# Logic.net
KiCad netlist of a schematic drawn in Altium Designer
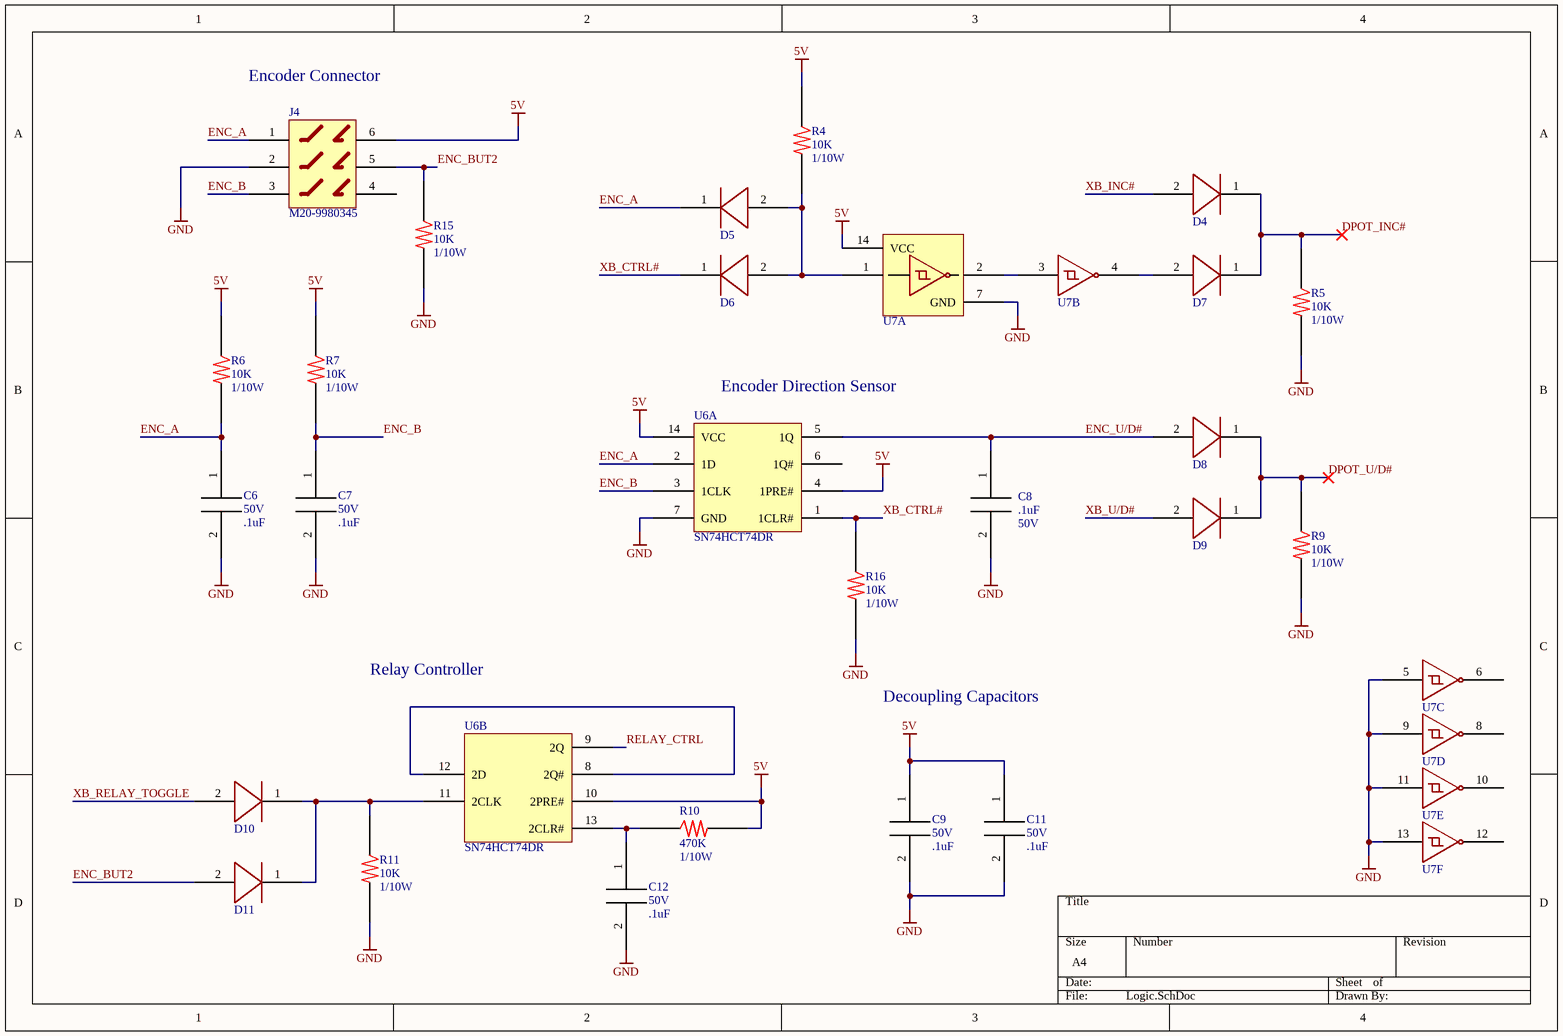
[diagram p0: Logic.SchDoc]

(export (version "E")
  (design (tool "Eeschema 10.0.6"))
  (components
    (comp (ref "C6")
      (value ".1uF")
      (footprint "0603")
      (fields
        (field (name "PARTNUMBER") "C0603C104K5RACAUTO")
        (field (name "MANUFACTURER") "KEMET")
        (field (name "RATING") "50V")
        (field (name "Comment") "C_CAP_0603")
      )
      (libsource (lib "SeniorProject") (part "C_CAP_0603"))
    )
    (comp (ref "C7")
      (value ".1uF")
      (footprint "0603")
      (fields
        (field (name "PARTNUMBER") "C0603C104K5RACAUTO")
        (field (name "MANUFACTURER") "KEMET")
        (field (name "RATING") "50V")
        (field (name "Comment") "C_CAP_0603")
      )
      (libsource (lib "SeniorProject") (part "C_CAP_0603"))
    )
    (comp (ref "C8")
      (value ".1uF")
      (footprint "0603")
      (fields
        (field (name "PARTNUMBER") "C0603C104K5RACAUTO")
        (field (name "MANUFACTURER") "KEMET")
        (field (name "RATING") "50V")
        (field (name "Comment") "C_CAP_0603")
      )
      (libsource (lib "SeniorProject") (part "C_CAP_0603"))
    )
    (comp (ref "C9")
      (value ".1uF")
      (footprint "0603")
      (fields
        (field (name "PARTNUMBER") "C0603C104K5RACAUTO")
        (field (name "MANUFACTURER") "KEMET")
        (field (name "RATING") "50V")
        (field (name "Comment") "C_CAP_0603")
      )
      (libsource (lib "SeniorProject") (part "C_CAP_0603"))
    )
    (comp (ref "C11")
      (value ".1uF")
      (footprint "0603")
      (fields
        (field (name "PARTNUMBER") "C0603C104K5RACAUTO")
        (field (name "MANUFACTURER") "KEMET")
        (field (name "RATING") "50V")
        (field (name "Comment") "C_CAP_0603")
      )
      (libsource (lib "SeniorProject") (part "C_CAP_0603"))
    )
    (comp (ref "C12")
      (value ".1uF")
      (footprint "0603")
      (fields
        (field (name "PARTNUMBER") "C0603C104K5RACAUTO")
        (field (name "MANUFACTURER") "KEMET")
        (field (name "RATING") "50V")
        (field (name "Comment") "C_CAP_0603")
      )
      (libsource (lib "SeniorProject") (part "C_CAP_0603"))
    )
    (comp (ref "D4")
      (value "D_DIODE_SOD123")
      (footprint "SOD123")
      (fields (field (name "PARTNUMBER") "BAS16GWJ") (field (name "MANUFACTURER") "Nexperia USA Inc"))
      (libsource (lib "SeniorProject") (part "D_DIODE_SOD123"))
    )
    (comp (ref "D5")
      (value "D_DIODE_SOD123")
      (footprint "SOD123")
      (fields (field (name "PARTNUMBER") "BAS16GWJ") (field (name "MANUFACTURER") "Nexperia USA Inc"))
      (libsource (lib "SeniorProject") (part "D_DIODE_SOD123"))
    )
    (comp (ref "D6")
      (value "D_DIODE_SOD123")
      (footprint "SOD123")
      (fields (field (name "PARTNUMBER") "BAS16GWJ") (field (name "MANUFACTURER") "Nexperia USA Inc"))
      (libsource (lib "SeniorProject") (part "D_DIODE_SOD123"))
    )
    (comp (ref "D7")
      (value "D_DIODE_SOD123")
      (footprint "SOD123")
      (fields (field (name "PARTNUMBER") "BAS16GWJ") (field (name "MANUFACTURER") "Nexperia USA Inc"))
      (libsource (lib "SeniorProject") (part "D_DIODE_SOD123"))
    )
    (comp (ref "D8")
      (value "D_DIODE_SOD123")
      (footprint "SOD123")
      (fields (field (name "PARTNUMBER") "BAS16GWJ") (field (name "MANUFACTURER") "Nexperia USA Inc"))
      (libsource (lib "SeniorProject") (part "D_DIODE_SOD123"))
    )
    (comp (ref "D9")
      (value "D_DIODE_SOD123")
      (footprint "SOD123")
      (fields (field (name "PARTNUMBER") "BAS16GWJ") (field (name "MANUFACTURER") "Nexperia USA Inc"))
      (libsource (lib "SeniorProject") (part "D_DIODE_SOD123"))
    )
    (comp (ref "D10")
      (value "D_DIODE_SOD123")
      (footprint "SOD123")
      (fields (field (name "PARTNUMBER") "BAS16GWJ") (field (name "MANUFACTURER") "Nexperia USA Inc"))
      (libsource (lib "SeniorProject") (part "D_DIODE_SOD123"))
    )
    (comp (ref "D11")
      (value "D_DIODE_SOD123")
      (footprint "SOD123")
      (fields (field (name "PARTNUMBER") "BAS16GWJ") (field (name "MANUFACTURER") "Nexperia USA Inc"))
      (libsource (lib "SeniorProject") (part "D_DIODE_SOD123"))
    )
    (comp (ref "J4")
      (value "J_6POSM_M20-9980345")
      (footprint "M20-9980345")
      (fields (field (name "MANUFACTURER") "Harwin") (field (name "PARTNUMBER") "M20-9980345"))
      (libsource (lib "SeniorProject") (part "J_6POSM_M20-9980345"))
    )
    (comp (ref "R4")
      (value "10K")
      (footprint "0603")
      (fields
        (field (name "PARTNUMBER") "RC0603JR-0710KL")
        (field (name "RATING") "1/10W")
        (field (name "Comment") "R_RES_0603")
      )
      (libsource (lib "SeniorProject") (part "R_RES_0603"))
    )
    (comp (ref "R5")
      (value "10K")
      (footprint "0603")
      (fields
        (field (name "PARTNUMBER") "RC0603JR-0710KL")
        (field (name "RATING") "1/10W")
        (field (name "Comment") "R_RES_0603")
      )
      (libsource (lib "SeniorProject") (part "R_RES_0603"))
    )
    (comp (ref "R6")
      (value "10K")
      (footprint "0603")
      (fields
        (field (name "PARTNUMBER") "RC0603JR-0710KL")
        (field (name "RATING") "1/10W")
        (field (name "Comment") "R_RES_0603")
      )
      (libsource (lib "SeniorProject") (part "R_RES_0603"))
    )
    (comp (ref "R7")
      (value "10K")
      (footprint "0603")
      (fields
        (field (name "PARTNUMBER") "RC0603JR-0710KL")
        (field (name "RATING") "1/10W")
        (field (name "Comment") "R_RES_0603")
      )
      (libsource (lib "SeniorProject") (part "R_RES_0603"))
    )
    (comp (ref "R9")
      (value "10K")
      (footprint "0603")
      (fields
        (field (name "PARTNUMBER") "RC0603JR-0710KL")
        (field (name "RATING") "1/10W")
        (field (name "Comment") "R_RES_0603")
      )
      (libsource (lib "SeniorProject") (part "R_RES_0603"))
    )
    (comp (ref "R10")
      (value "470K")
      (footprint "0603")
      (fields
        (field (name "PARTNUMBER") "RC0603JR-07470KL")
        (field (name "MANUFACTURER") "Yageo")
        (field (name "RATING") "1/10W")
        (field (name "Comment") "R_RES_0603")
      )
      (libsource (lib "SeniorProject") (part "R_RES_0603"))
    )
    (comp (ref "R11")
      (value "10K")
      (footprint "0603")
      (fields
        (field (name "PARTNUMBER") "RC0603JR-0710KL")
        (field (name "RATING") "1/10W")
        (field (name "Comment") "R_RES_0603")
      )
      (libsource (lib "SeniorProject") (part "R_RES_0603"))
    )
    (comp (ref "R15")
      (value "10K")
      (footprint "0603")
      (fields
        (field (name "PARTNUMBER") "RC0603JR-0710KL")
        (field (name "RATING") "1/10W")
        (field (name "Comment") "R_RES_0603")
      )
      (libsource (lib "SeniorProject") (part "R_RES_0603"))
    )
    (comp (ref "R16")
      (value "10K")
      (footprint "0603")
      (fields
        (field (name "PARTNUMBER") "RC0603JR-0710KL")
        (field (name "RATING") "1/10W")
        (field (name "Comment") "R_RES_0603")
      )
      (libsource (lib "SeniorProject") (part "R_RES_0603"))
    )
    (comp (ref "U6")
      (value "U_DUALDFLIP_SOIC14")
      (footprint "SOIC14")
      (fields (field (name "MANUFACTURER") "TI") (field (name "PARTNUMBER") "SN74HCT74DR"))
      (libsource (lib "SeniorProject") (part "U_DUALDFLIP_SOIC14"))
    )
    (comp (ref "U7")
      (value "U_SN74HCT04DR_SOIC14")
      (footprint "SOIC14")
      (fields (field (name "PARTNUMBER") "SN74HCT04DR") (field (name "MANUFACTURER") "TI"))
      (libsource (lib "SeniorProject") (part "U_SN74HCT04DR_SOIC14"))
    )
  )
  (nets
    (net (code "1") (name "/DPOT_INC#") (class "Default")
      (node (ref "D4") (pin "1") (pintype "passive"))
      (node (ref "D7") (pin "1") (pintype "passive"))
      (node (ref "R5") (pin "1") (pintype "passive"))
    )
    (net (code "2") (name "/DPOT_U{slash}D#") (class "Default")
      (node (ref "D8") (pin "1") (pintype "passive"))
      (node (ref "D9") (pin "1") (pintype "passive"))
      (node (ref "R9") (pin "1") (pintype "passive"))
    )
    (net (code "3") (name "/ENC_A") (class "Default")
      (node (ref "C6") (pin "1") (pintype "passive"))
      (node (ref "D5") (pin "1") (pintype "passive"))
      (node (ref "J4") (pin "1") (pinfunction "1_1") (pintype "passive"))
      (node (ref "R6") (pin "2") (pintype "passive"))
      (node (ref "U6") (pin "2") (pinfunction "1D_2") (pintype "passive"))
    )
    (net (code "4") (name "/ENC_B") (class "Default")
      (node (ref "C7") (pin "1") (pintype "passive"))
      (node (ref "J4") (pin "3") (pinfunction "3_3") (pintype "passive"))
      (node (ref "R7") (pin "2") (pintype "passive"))
      (node (ref "U6") (pin "3") (pinfunction "1CLK_3") (pintype "passive"))
    )
    (net (code "5") (name "/ENC_BUT2") (class "Default")
      (node (ref "D11") (pin "2") (pintype "passive"))
      (node (ref "J4") (pin "5") (pinfunction "5_5") (pintype "passive"))
      (node (ref "R15") (pin "1") (pintype "passive"))
    )
    (net (code "6") (name "/ENC_U{slash}D#") (class "Default")
      (node (ref "C8") (pin "1") (pintype "passive"))
      (node (ref "D8") (pin "2") (pintype "passive"))
      (node (ref "U6") (pin "5") (pinfunction "1Q_5") (pintype "passive"))
    )
    (net (code "7") (name "/RELAY_CTRL") (class "Default")
      (node (ref "U6") (pin "9") (pinfunction "2Q_9") (pintype "passive"))
    )
    (net (code "8") (name "/XB_CTRL#") (class "Default")
      (node (ref "D6") (pin "1") (pintype "passive"))
      (node (ref "R16") (pin "1") (pintype "passive"))
      (node (ref "U6") (pin "1") (pinfunction "1CLR#_1") (pintype "passive"))
    )
    (net (code "9") (name "/XB_INC#") (class "Default") (node (ref "D4") (pin "2") (pintype "passive")))
    (net (code "10") (name "/XB_RELAY_TOGGLE") (class "Default")
      (node (ref "D10") (pin "2") (pintype "passive"))
    )
    (net (code "11") (name "/XB_U{slash}D#") (class "Default")
      (node (ref "D9") (pin "2") (pintype "passive"))
    )
    (net (code "12") (name "5V") (class "Default")
      (node (ref "C11") (pin "1") (pintype "passive"))
      (node (ref "C9") (pin "1") (pintype "passive"))
      (node (ref "J4") (pin "6") (pinfunction "6_6") (pintype "passive"))
      (node (ref "R10") (pin "2") (pintype "passive"))
      (node (ref "R4") (pin "1") (pintype "passive"))
      (node (ref "R6") (pin "1") (pintype "passive"))
      (node (ref "R7") (pin "1") (pintype "passive"))
      (node (ref "U6") (pin "10") (pinfunction "2PRE#_10") (pintype "passive"))
      (node (ref "U6") (pin "14") (pinfunction "VCC_14") (pintype "passive"))
      (node (ref "U6") (pin "4") (pinfunction "1PRE#_4") (pintype "passive"))
      (node (ref "U7") (pin "14") (pinfunction "VCC_14") (pintype "passive"))
    )
    (net (code "13") (name "GND") (class "Default")
      (node (ref "C11") (pin "2") (pintype "passive"))
      (node (ref "C12") (pin "2") (pintype "passive"))
      (node (ref "C6") (pin "2") (pintype "passive"))
      (node (ref "C7") (pin "2") (pintype "passive"))
      (node (ref "C8") (pin "2") (pintype "passive"))
      (node (ref "C9") (pin "2") (pintype "passive"))
      (node (ref "J4") (pin "2") (pinfunction "2_2") (pintype "passive"))
      (node (ref "R11") (pin "2") (pintype "passive"))
      (node (ref "R15") (pin "2") (pintype "passive"))
      (node (ref "R16") (pin "2") (pintype "passive"))
      (node (ref "R5") (pin "2") (pintype "passive"))
      (node (ref "R9") (pin "2") (pintype "passive"))
      (node (ref "U6") (pin "7") (pinfunction "GND_7") (pintype "passive"))
      (node (ref "U7") (pin "11") (pintype "passive"))
      (node (ref "U7") (pin "13") (pintype "passive"))
      (node (ref "U7") (pin "5") (pintype "passive"))
      (node (ref "U7") (pin "7") (pinfunction "GND_7") (pintype "passive"))
      (node (ref "U7") (pin "9") (pintype "passive"))
    )
    (net (code "14") (name "Net-(D5-Pad2)") (class "Default")
      (node (ref "D5") (pin "2") (pintype "passive"))
      (node (ref "D6") (pin "2") (pintype "passive"))
      (node (ref "R4") (pin "2") (pintype "passive"))
      (node (ref "U7") (pin "1") (pintype "passive"))
    )
    (net (code "15") (name "Net-(D7-Pad2)") (class "Default")
      (node (ref "D7") (pin "2") (pintype "passive"))
      (node (ref "U7") (pin "4") (pintype "passive"))
    )
    (net (code "16") (name "Net-(U6B-2CLK)") (class "Default")
      (node (ref "D10") (pin "1") (pintype "passive"))
      (node (ref "D11") (pin "1") (pintype "passive"))
      (node (ref "R11") (pin "1") (pintype "passive"))
      (node (ref "U6") (pin "11") (pinfunction "2CLK_11") (pintype "passive"))
    )
    (net (code "17") (name "Net-(U6B-2CLR#)") (class "Default")
      (node (ref "C12") (pin "1") (pintype "passive"))
      (node (ref "R10") (pin "1") (pintype "passive"))
      (node (ref "U6") (pin "13") (pinfunction "2CLR#_13") (pintype "passive"))
    )
    (net (code "18") (name "Net-(U6B-2D)") (class "Default")
      (node (ref "U6") (pin "12") (pinfunction "2D_12") (pintype "passive"))
      (node (ref "U6") (pin "8") (pinfunction "2Q#_8") (pintype "passive"))
    )
    (net (code "19") (name "Net-(U7-Pad2)") (class "Default")
      (node (ref "U7") (pin "2") (pintype "passive"))
      (node (ref "U7") (pin "3") (pintype "passive"))
    )
    (net (code "20") (name "unconnected-(J4-Pad4)") (class "Default")
      (node (ref "J4") (pin "4") (pinfunction "4_4") (pintype "passive"))
    )
    (net (code "21") (name "unconnected-(U6A-1Q#-Pad6)") (class "Default")
      (node (ref "U6") (pin "6") (pinfunction "1Q#_6") (pintype "passive"))
    )
    (net (code "22") (name "unconnected-(U7-Pad6)") (class "Default")
      (node (ref "U7") (pin "6") (pintype "passive"))
    )
    (net (code "23") (name "unconnected-(U7-Pad8)") (class "Default")
      (node (ref "U7") (pin "8") (pintype "passive"))
    )
    (net (code "24") (name "unconnected-(U7-Pad10)") (class "Default")
      (node (ref "U7") (pin "10") (pintype "passive"))
    )
    (net (code "25") (name "unconnected-(U7-Pad12)") (class "Default")
      (node (ref "U7") (pin "12") (pintype "passive"))
    )
  )
)
